# ssd1963.net
KiCad netlist of a schematic drawn in Altium Designer
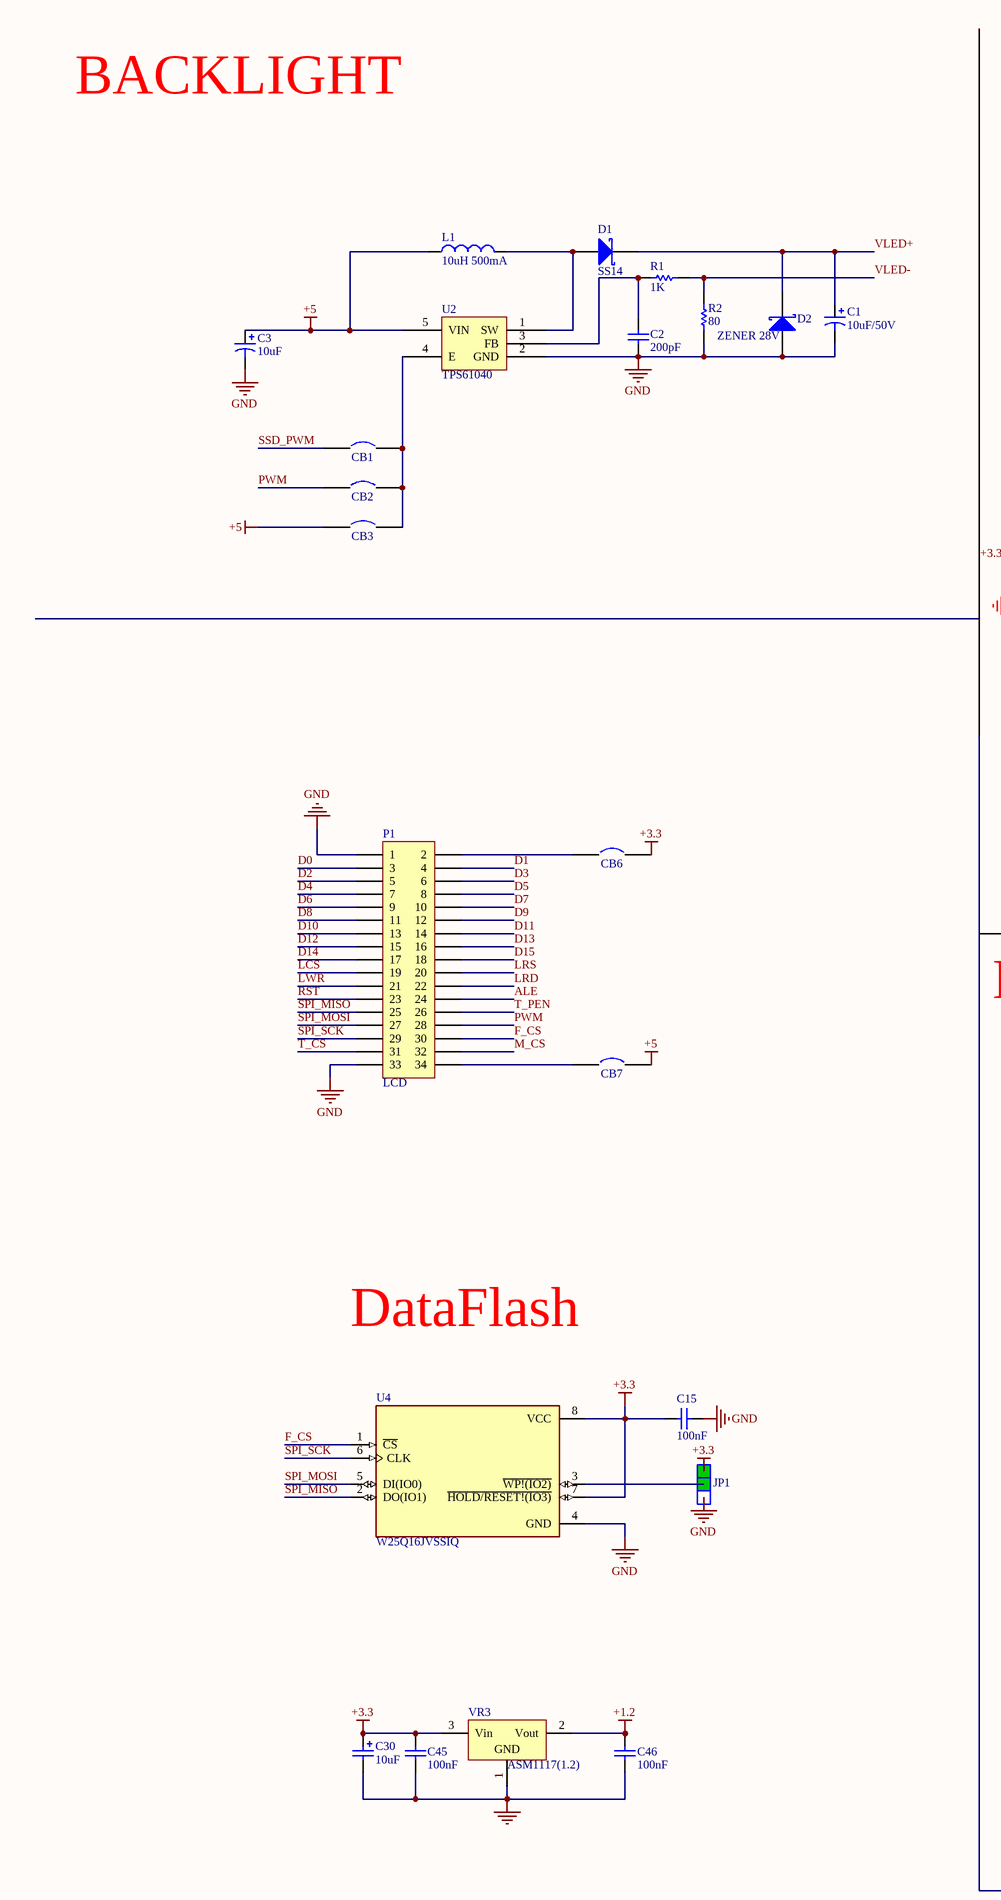
[diagram p0: ssd1963.SchDoc, left]
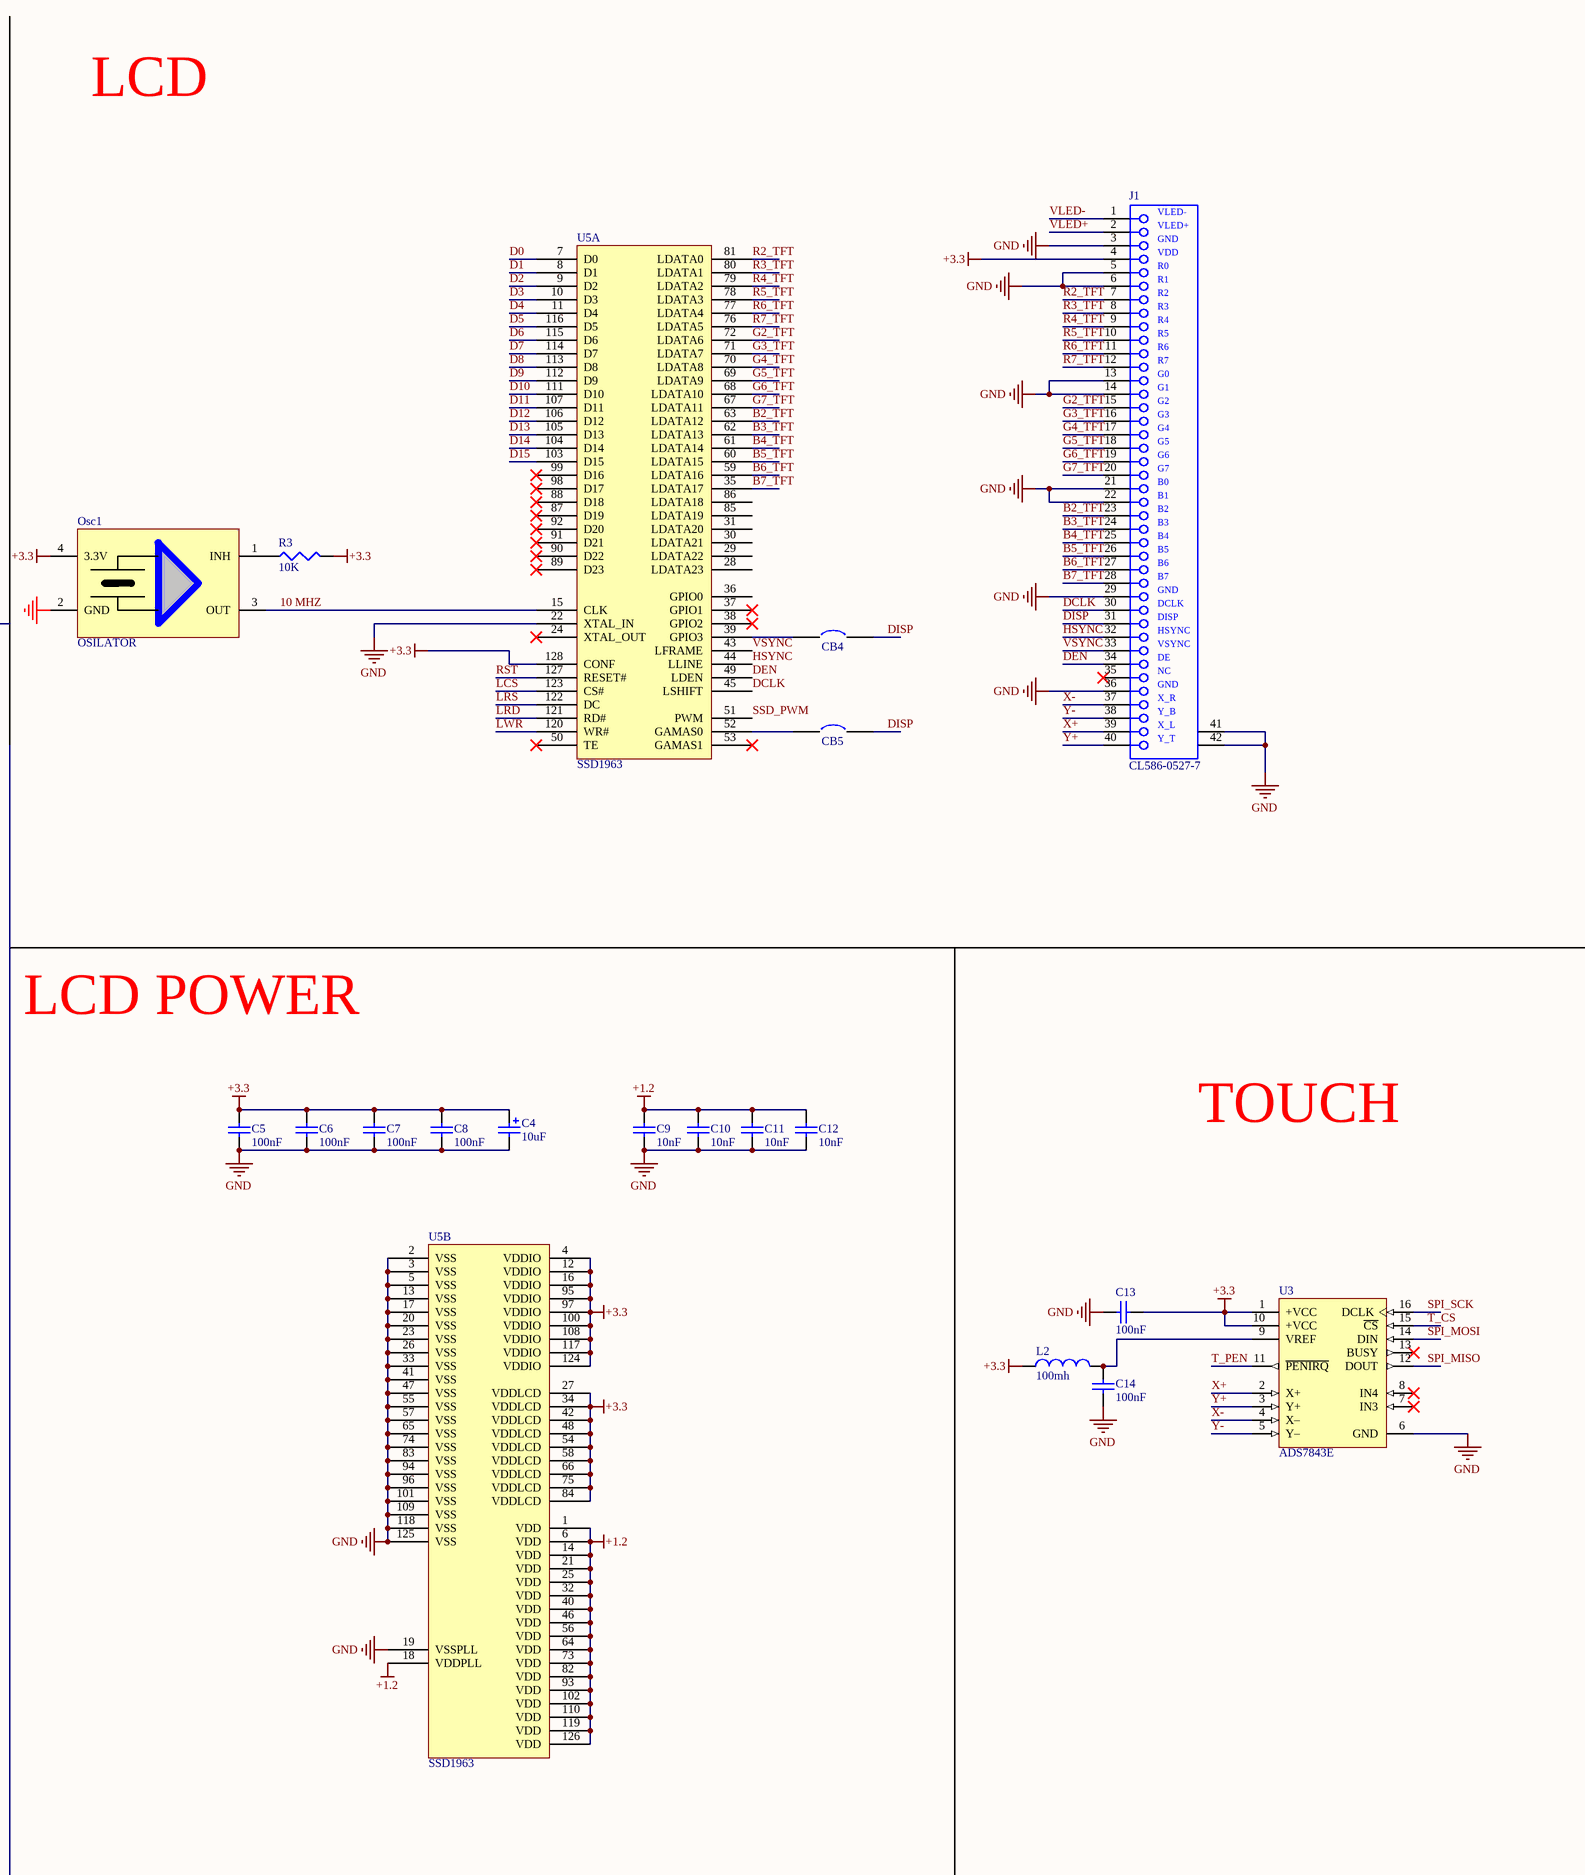
[diagram p1: ssd1963.SchDoc, right]

(export (version "E")
  (design (tool "Eeschema 10.0.6"))
  (components
    (comp (ref "C1")
      (value "10uF/50V")
      (footprint "Tantalium Size A")
      (description "Polarized Capacitor (Radial)")
      (fields (field (name "PUBLISHER") "Altium Limited"))
      (libsource (lib "Miscellaneous Devices") (part "Cap Pol1"))
    )
    (comp (ref "C2")
      (value "200pF")
      (footprint "0805")
      (description "Capacitor (Semiconductor SIM Model)")
      (fields (field (name "PUBLISHER") "Altium Limited"))
      (libsource (lib "Miscellaneous Devices") (part "Cap Semi"))
    )
    (comp (ref "C3")
      (value "10uF")
      (footprint "Tantalium Size A")
      (description "Polarized Capacitor (Radial)")
      (fields (field (name "PUBLISHER") "Altium Limited"))
      (libsource (lib "Miscellaneous Devices") (part "Cap Pol1"))
    )
    (comp (ref "C4")
      (value "10uF")
      (footprint "Tantalium Size A")
      (description "Polarized Capacitor (Radial)")
      (fields (field (name "PUBLISHER") "Altium Limited"))
      (libsource (lib "") (part "Cap Pol1_1"))
    )
    (comp (ref "C5")
      (value "100nF")
      (footprint "0805")
      (description "Capacitor")
      (fields (field (name "PUBLISHER") "Altium Limited"))
      (libsource (lib "Miscellaneous Devices") (part "Cap"))
    )
    (comp (ref "C6")
      (value "100nF")
      (footprint "0805")
      (description "Capacitor")
      (fields (field (name "PUBLISHER") "Altium Limited"))
      (libsource (lib "Miscellaneous Devices") (part "Cap"))
    )
    (comp (ref "C7")
      (value "100nF")
      (footprint "0805")
      (description "Capacitor")
      (fields (field (name "PUBLISHER") "Altium Limited"))
      (libsource (lib "Miscellaneous Devices") (part "Cap"))
    )
    (comp (ref "C8")
      (value "100nF")
      (footprint "0805")
      (description "Capacitor")
      (fields (field (name "PUBLISHER") "Altium Limited"))
      (libsource (lib "Miscellaneous Devices") (part "Cap"))
    )
    (comp (ref "C9")
      (value "10nF")
      (footprint "0805")
      (description "Capacitor")
      (fields (field (name "PUBLISHER") "Altium Limited"))
      (libsource (lib "Miscellaneous Devices") (part "Cap"))
    )
    (comp (ref "C10")
      (value "10nF")
      (footprint "0805")
      (description "Capacitor")
      (fields (field (name "PUBLISHER") "Altium Limited"))
      (libsource (lib "Miscellaneous Devices") (part "Cap"))
    )
    (comp (ref "C11")
      (value "10nF")
      (footprint "0805")
      (description "Capacitor")
      (fields (field (name "PUBLISHER") "Altium Limited"))
      (libsource (lib "Miscellaneous Devices") (part "Cap"))
    )
    (comp (ref "C12")
      (value "10nF")
      (footprint "0805")
      (description "Capacitor")
      (fields (field (name "PUBLISHER") "Altium Limited"))
      (libsource (lib "Miscellaneous Devices") (part "Cap"))
    )
    (comp (ref "C13")
      (value "100nF")
      (footprint "0805")
      (description "Capacitor")
      (fields (field (name "PUBLISHER") "Altium Limited"))
      (libsource (lib "Miscellaneous Devices") (part "Cap"))
    )
    (comp (ref "C14")
      (value "100nF")
      (footprint "0805")
      (description "Capacitor")
      (fields (field (name "PUBLISHER") "Altium Limited"))
      (libsource (lib "Miscellaneous Devices") (part "Cap"))
    )
    (comp (ref "C15")
      (value "100nF")
      (footprint "0805")
      (description "Capacitor")
      (fields (field (name "PUBLISHER") "Altium Limited"))
      (libsource (lib "Miscellaneous Devices") (part "Cap"))
    )
    (comp (ref "C30")
      (value "10uF")
      (footprint "Tantalium Size A")
      (description "Polarized Capacitor (Radial)")
      (fields (field (name "PUBLISHER") "Altium Limited"))
      (libsource (lib "") (part "Cap Pol1_1"))
    )
    (comp (ref "C45")
      (value "100nF")
      (footprint "0805")
      (description "Capacitor")
      (fields (field (name "PUBLISHER") "Altium Limited"))
      (libsource (lib "Miscellaneous Devices") (part "Cap"))
    )
    (comp (ref "C46")
      (value "100nF")
      (footprint "0805")
      (description "Capacitor")
      (fields (field (name "PUBLISHER") "Altium Limited"))
      (libsource (lib "Miscellaneous Devices") (part "Cap"))
    )
    (comp (ref "CB1")
      (value "JUMPER")
      (footprint "0805")
      (description "Circuit Breaker")
      (fields (field (name "PUBLISHER") "Altium Limited"))
      (libsource (lib "Miscellaneous Devices") (part "Circuit Breaker"))
    )
    (comp (ref "CB2")
      (value "JUMPER")
      (footprint "0805")
      (description "Circuit Breaker")
      (fields (field (name "PUBLISHER") "Altium Limited"))
      (libsource (lib "Miscellaneous Devices") (part "Circuit Breaker"))
    )
    (comp (ref "CB3")
      (value "JUMPER")
      (footprint "0805")
      (description "Circuit Breaker")
      (fields (field (name "PUBLISHER") "Altium Limited"))
      (libsource (lib "Miscellaneous Devices") (part "Circuit Breaker"))
    )
    (comp (ref "CB4")
      (value "JUMPER")
      (footprint "0805")
      (description "Circuit Breaker")
      (fields (field (name "PUBLISHER") "Altium Limited"))
      (libsource (lib "Miscellaneous Devices") (part "Circuit Breaker"))
    )
    (comp (ref "CB5")
      (value "JUMPER")
      (footprint "0805")
      (description "Circuit Breaker")
      (fields (field (name "PUBLISHER") "Altium Limited"))
      (libsource (lib "Miscellaneous Devices") (part "Circuit Breaker"))
    )
    (comp (ref "CB6")
      (value "JUMPER")
      (footprint "0805")
      (description "Circuit Breaker")
      (fields (field (name "PUBLISHER") "Altium Limited"))
      (libsource (lib "Miscellaneous Devices") (part "Circuit Breaker"))
    )
    (comp (ref "CB7")
      (value "JUMPER")
      (footprint "0805")
      (description "Circuit Breaker")
      (fields (field (name "PUBLISHER") "Altium Limited"))
      (libsource (lib "Miscellaneous Devices") (part "Circuit Breaker"))
    )
    (comp (ref "D1")
      (value "SS14")
      (footprint "1N4004SMD")
      (description "Schottky Diode")
      (fields (field (name "PUBLISHER") "Altium Limited"))
      (libsource (lib "Miscellaneous Devices") (part "D Schottky"))
    )
    (comp (ref "D2")
      (value "ZENER 28V")
      (footprint "1N4004SMD")
      (description "Schottky Diode")
      (fields (field (name "PUBLISHER") "Altium Limited"))
      (libsource (lib "Miscellaneous Devices") (part "D Schottky"))
    )
    (comp (ref "J1")
      (value "CL586-0527-7")
      (footprint "FPC_40PIN")
      (description "FH12 Series, \"Flip-Lock\" SMT/ZIF FFC/FPC Connector - 0.5mm Spaced Bottom Contact")
      (fields (field (name "PUBLISHER") "Altium Limited"))
      (libsource (lib "Schlib1") (part "CL586-0527-7"))
    )
    (comp (ref "JP1")
      (value "Jumper")
      (footprint "JT3")
      (description "Jumper Selector")
      (libsource (lib "Electrovolt Lib") (part "Jumper Selector"))
    )
    (comp (ref "L1")
      (value "10uH 500mA")
      (footprint "INDUCT100UH B")
      (description "Inductor")
      (fields (field (name "PUBLISHER") "Altium Limited"))
      (libsource (lib "Miscellaneous Devices") (part "Inductor"))
    )
    (comp (ref "L2")
      (value "100mh")
      (footprint "1206")
      (description "Inductor")
      (fields (field (name "PUBLISHER") "Altium Limited"))
      (libsource (lib "Miscellaneous Devices") (part "Inductor"))
    )
    (comp (ref "Osc1")
      (value "OSILATOR")
      (footprint "XTAL_5X7")
      (libsource (lib "New Lib") (part "OSILATOR"))
    )
    (comp (ref "P1")
      (value "LCD")
      (footprint "HDR2X17")
      (description "Header, 17-Pin, Dual row")
      (fields (field (name "PUBLISHER") "Altium Limited"))
      (libsource (lib "Miscellaneous Connectors") (part "Header 17X2"))
    )
    (comp (ref "R1")
      (value "1K")
      (footprint "0805")
      (description "Resistor")
      (fields (field (name "PUBLISHER") "Altium Limited"))
      (libsource (lib "Miscellaneous Devices") (part "Res1"))
    )
    (comp (ref "R2")
      (value "80")
      (footprint "0805")
      (description "Resistor")
      (fields (field (name "PUBLISHER") "Altium Limited"))
      (libsource (lib "Miscellaneous Devices") (part "Res1"))
    )
    (comp (ref "R3")
      (value "10K")
      (footprint "0805")
      (description "Resistor")
      (fields (field (name "PUBLISHER") "Altium Limited"))
      (libsource (lib "Miscellaneous Devices") (part "Res3"))
    )
    (comp (ref "U2")
      (value "TPS61040")
      (footprint "TPS61040")
      (description "Backlight Regulagtor")
      (libsource (lib "Schlib1") (part "TPS61040"))
    )
    (comp (ref "U3")
      (value "ADS7843E")
      (footprint "DBQ016")
      (description "4-Wire Touch Screen Controller, 16-Pin SSOP, Pb-Free")
      (fields (field (name "PUBLISHER") "Altium Limited"))
      (libsource (lib "TI Interface Touch Screen Controller") (part "ADS7843E"))
    )
    (comp (ref "U4")
      (value "W25Q16JVSSIQ")
      (footprint "SOIC127P790X216-8N")
      (description "FLASH - NOR Memory IC 16Mb _2M x 8_ SPI - Quad I/O 133MHz 8-SOIC")
      (fields (field (name "MF") "Winbond Electronics"))
      (libsource (lib "W25Q16JVSSIQ") (part "W25Q16JVSSIQ"))
    )
    (comp (ref "U5")
      (value "SSD1963")
      (footprint "TSQFP40P1600X1600-128N")
      (libsource (lib "Schlib1") (part "SSD1963"))
    )
    (comp (ref "VR3")
      (value "ASM1117(1.2)")
      (footprint "ASM1117")
      (description "Voltage Regulator")
      (fields (field (name "PUBLISHER") "Altium Limited"))
      (libsource (lib "Miscellaneous Devices") (part "Volt Reg_1"))
    )
  )
  (nets
    (net (code "1") (name "+1.2") (class "Default")
      (node (ref "C10") (pin "1") (pinfunction "1_1") (pintype "passive"))
      (node (ref "C11") (pin "1") (pinfunction "1_1") (pintype "passive"))
      (node (ref "C12") (pin "1") (pinfunction "1_1") (pintype "passive"))
      (node (ref "C46") (pin "1") (pinfunction "1_1") (pintype "passive"))
      (node (ref "C9") (pin "1") (pinfunction "1_1") (pintype "passive"))
      (node (ref "U5") (pin "1") (pinfunction "VDD_1") (pintype "power_in"))
      (node (ref "U5") (pin "102") (pinfunction "VDD_102") (pintype "power_in"))
      (node (ref "U5") (pin "110") (pinfunction "VDD_110") (pintype "power_in"))
      (node (ref "U5") (pin "119") (pinfunction "VDD_119") (pintype "power_in"))
      (node (ref "U5") (pin "126") (pinfunction "VDD_126") (pintype "power_in"))
      (node (ref "U5") (pin "14") (pinfunction "VDD_14") (pintype "power_in"))
      (node (ref "U5") (pin "18") (pinfunction "VDDPLL_18") (pintype "power_in"))
      (node (ref "U5") (pin "21") (pinfunction "VDD_21") (pintype "power_in"))
      (node (ref "U5") (pin "25") (pinfunction "VDD_25") (pintype "power_in"))
      (node (ref "U5") (pin "32") (pinfunction "VDD_32") (pintype "power_in"))
      (node (ref "U5") (pin "40") (pinfunction "VDD_40") (pintype "power_in"))
      (node (ref "U5") (pin "46") (pinfunction "VDD_46") (pintype "power_in"))
      (node (ref "U5") (pin "56") (pinfunction "VDD_56") (pintype "power_in"))
      (node (ref "U5") (pin "6") (pinfunction "VDD_6") (pintype "power_in"))
      (node (ref "U5") (pin "64") (pinfunction "VDD_64") (pintype "power_in"))
      (node (ref "U5") (pin "73") (pinfunction "VDD_73") (pintype "power_in"))
      (node (ref "U5") (pin "82") (pinfunction "VDD_82") (pintype "power_in"))
      (node (ref "U5") (pin "93") (pinfunction "VDD_93") (pintype "power_in"))
      (node (ref "VR3") (pin "2") (pinfunction "Vout_2") (pintype "passive"))
    )
    (net (code "2") (name "+3.3") (class "Default")
      (node (ref "C13") (pin "2") (pinfunction "2_2") (pintype "passive"))
      (node (ref "C15") (pin "1") (pinfunction "1_1") (pintype "passive"))
      (node (ref "C30") (pin "1") (pinfunction "1_1") (pintype "passive"))
      (node (ref "C4") (pin "1") (pinfunction "1_1") (pintype "passive"))
      (node (ref "C45") (pin "1") (pinfunction "1_1") (pintype "passive"))
      (node (ref "C5") (pin "1") (pinfunction "1_1") (pintype "passive"))
      (node (ref "C6") (pin "1") (pinfunction "1_1") (pintype "passive"))
      (node (ref "C7") (pin "1") (pinfunction "1_1") (pintype "passive"))
      (node (ref "C8") (pin "1") (pinfunction "1_1") (pintype "passive"))
      (node (ref "CB6") (pin "2") (pinfunction "2_2") (pintype "passive"))
      (node (ref "J1") (pin "4") (pinfunction "4_4") (pintype "passive"))
      (node (ref "JP1") (pin "1") (pinfunction "1_1") (pintype "passive"))
      (node (ref "L2") (pin "1") (pinfunction "1_1") (pintype "passive"))
      (node (ref "Osc1") (pin "4") (pinfunction "3.3V_4") (pintype "passive"))
      (node (ref "R3") (pin "2") (pinfunction "2_2") (pintype "passive"))
      (node (ref "U3") (pin "1") (pinfunction "+VCC_1") (pintype "power_in"))
      (node (ref "U3") (pin "10") (pinfunction "+VCC_10") (pintype "power_in"))
      (node (ref "U4") (pin "7") (pinfunction "~{HOLD/RESET!(IO3)}_7") (pintype "bidirectional"))
      (node (ref "U4") (pin "8") (pinfunction "VCC_8") (pintype "power_in"))
      (node (ref "U5") (pin "100") (pinfunction "VDDIO_100") (pintype "power_in"))
      (node (ref "U5") (pin "108") (pinfunction "VDDIO_108") (pintype "power_in"))
      (node (ref "U5") (pin "117") (pinfunction "VDDIO_117") (pintype "power_in"))
      (node (ref "U5") (pin "12") (pinfunction "VDDIO_12") (pintype "power_in"))
      (node (ref "U5") (pin "124") (pinfunction "VDDIO_124") (pintype "power_in"))
      (node (ref "U5") (pin "128") (pinfunction "CONF_128") (pintype "passive"))
      (node (ref "U5") (pin "16") (pinfunction "VDDIO_16") (pintype "power_in"))
      (node (ref "U5") (pin "27") (pinfunction "VDDLCD_27") (pintype "power_in"))
      (node (ref "U5") (pin "34") (pinfunction "VDDLCD_34") (pintype "power_in"))
      (node (ref "U5") (pin "4") (pinfunction "VDDIO_4") (pintype "power_in"))
      (node (ref "U5") (pin "42") (pinfunction "VDDLCD_42") (pintype "power_in"))
      (node (ref "U5") (pin "48") (pinfunction "VDDLCD_48") (pintype "power_in"))
      (node (ref "U5") (pin "54") (pinfunction "VDDLCD_54") (pintype "power_in"))
      (node (ref "U5") (pin "58") (pinfunction "VDDLCD_58") (pintype "power_in"))
      (node (ref "U5") (pin "66") (pinfunction "VDDLCD_66") (pintype "power_in"))
      (node (ref "U5") (pin "75") (pinfunction "VDDLCD_75") (pintype "power_in"))
      (node (ref "U5") (pin "84") (pinfunction "VDDLCD_84") (pintype "power_in"))
      (node (ref "U5") (pin "95") (pinfunction "VDDIO_95") (pintype "power_in"))
      (node (ref "U5") (pin "97") (pinfunction "VDDIO_97") (pintype "power_in"))
      (node (ref "VR3") (pin "3") (pinfunction "Vin_3") (pintype "passive"))
    )
    (net (code "3") (name "+5") (class "Default")
      (node (ref "C3") (pin "1") (pinfunction "1_1") (pintype "passive"))
      (node (ref "CB3") (pin "1") (pinfunction "1_1") (pintype "passive"))
      (node (ref "CB7") (pin "2") (pinfunction "2_2") (pintype "passive"))
      (node (ref "L1") (pin "1") (pinfunction "1_1") (pintype "passive"))
      (node (ref "U2") (pin "5") (pinfunction "VIN_5") (pintype "passive"))
    )
    (net (code "4") (name "/10 MHZ") (class "Default")
      (node (ref "Osc1") (pin "3") (pinfunction "OUT_3") (pintype "passive"))
      (node (ref "U5") (pin "15") (pinfunction "CLK_15") (pintype "power_in"))
    )
    (net (code "5") (name "/ALE") (class "Default")
      (node (ref "P1") (pin "24") (pinfunction "24_24") (pintype "passive"))
    )
    (net (code "6") (name "/B2_TFT") (class "Default")
      (node (ref "J1") (pin "23") (pinfunction "23_23") (pintype "passive"))
      (node (ref "U5") (pin "63") (pinfunction "LDATA12_63") (pintype "power_in"))
    )
    (net (code "7") (name "/B3_TFT") (class "Default")
      (node (ref "J1") (pin "24") (pinfunction "24_24") (pintype "passive"))
      (node (ref "U5") (pin "62") (pinfunction "LDATA13_62") (pintype "power_in"))
    )
    (net (code "8") (name "/B4_TFT") (class "Default")
      (node (ref "J1") (pin "25") (pinfunction "25_25") (pintype "passive"))
      (node (ref "U5") (pin "61") (pinfunction "LDATA14_61") (pintype "power_in"))
    )
    (net (code "9") (name "/B5_TFT") (class "Default")
      (node (ref "J1") (pin "26") (pinfunction "26_26") (pintype "passive"))
      (node (ref "U5") (pin "60") (pinfunction "LDATA15_60") (pintype "power_in"))
    )
    (net (code "10") (name "/B6_TFT") (class "Default")
      (node (ref "J1") (pin "27") (pinfunction "27_27") (pintype "passive"))
      (node (ref "U5") (pin "59") (pinfunction "LDATA16_59") (pintype "power_in"))
    )
    (net (code "11") (name "/B7_TFT") (class "Default")
      (node (ref "J1") (pin "28") (pinfunction "28_28") (pintype "passive"))
      (node (ref "U5") (pin "35") (pinfunction "LDATA17_35") (pintype "power_in"))
    )
    (net (code "12") (name "/D0") (class "Default")
      (node (ref "P1") (pin "3") (pinfunction "3_3") (pintype "passive"))
      (node (ref "U5") (pin "7") (pinfunction "D0_7") (pintype "power_in"))
    )
    (net (code "13") (name "/D1") (class "Default")
      (node (ref "P1") (pin "4") (pinfunction "4_4") (pintype "passive"))
      (node (ref "U5") (pin "8") (pinfunction "D1_8") (pintype "power_in"))
    )
    (net (code "14") (name "/D2") (class "Default")
      (node (ref "P1") (pin "5") (pinfunction "5_5") (pintype "passive"))
      (node (ref "U5") (pin "9") (pinfunction "D2_9") (pintype "power_in"))
    )
    (net (code "15") (name "/D3") (class "Default")
      (node (ref "P1") (pin "6") (pinfunction "6_6") (pintype "passive"))
      (node (ref "U5") (pin "10") (pinfunction "D3_10") (pintype "power_in"))
    )
    (net (code "16") (name "/D4") (class "Default")
      (node (ref "P1") (pin "7") (pinfunction "7_7") (pintype "passive"))
      (node (ref "U5") (pin "11") (pinfunction "D4_11") (pintype "power_in"))
    )
    (net (code "17") (name "/D5") (class "Default")
      (node (ref "P1") (pin "8") (pinfunction "8_8") (pintype "passive"))
      (node (ref "U5") (pin "116") (pinfunction "D5_116") (pintype "power_in"))
    )
    (net (code "18") (name "/D6") (class "Default")
      (node (ref "P1") (pin "9") (pinfunction "9_9") (pintype "passive"))
      (node (ref "U5") (pin "115") (pinfunction "D6_115") (pintype "power_in"))
    )
    (net (code "19") (name "/D7") (class "Default")
      (node (ref "P1") (pin "10") (pinfunction "10_10") (pintype "passive"))
      (node (ref "U5") (pin "114") (pinfunction "D7_114") (pintype "power_in"))
    )
    (net (code "20") (name "/D8") (class "Default")
      (node (ref "P1") (pin "11") (pinfunction "11_11") (pintype "passive"))
      (node (ref "U5") (pin "113") (pinfunction "D8_113") (pintype "power_in"))
    )
    (net (code "21") (name "/D9") (class "Default")
      (node (ref "P1") (pin "12") (pinfunction "12_12") (pintype "passive"))
      (node (ref "U5") (pin "112") (pinfunction "D9_112") (pintype "power_in"))
    )
    (net (code "22") (name "/D10") (class "Default")
      (node (ref "P1") (pin "13") (pinfunction "13_13") (pintype "passive"))
      (node (ref "U5") (pin "111") (pinfunction "D10_111") (pintype "power_in"))
    )
    (net (code "23") (name "/D11") (class "Default")
      (node (ref "P1") (pin "14") (pinfunction "14_14") (pintype "passive"))
      (node (ref "U5") (pin "107") (pinfunction "D11_107") (pintype "power_in"))
    )
    (net (code "24") (name "/D12") (class "Default")
      (node (ref "P1") (pin "15") (pinfunction "15_15") (pintype "passive"))
      (node (ref "U5") (pin "106") (pinfunction "D12_106") (pintype "power_in"))
    )
    (net (code "25") (name "/D13") (class "Default")
      (node (ref "P1") (pin "16") (pinfunction "16_16") (pintype "passive"))
      (node (ref "U5") (pin "105") (pinfunction "D13_105") (pintype "power_in"))
    )
    (net (code "26") (name "/D14") (class "Default")
      (node (ref "P1") (pin "17") (pinfunction "17_17") (pintype "passive"))
      (node (ref "U5") (pin "104") (pinfunction "D14_104") (pintype "power_in"))
    )
    (net (code "27") (name "/D15") (class "Default")
      (node (ref "P1") (pin "18") (pinfunction "18_18") (pintype "passive"))
      (node (ref "U5") (pin "103") (pinfunction "D15_103") (pintype "power_in"))
    )
    (net (code "28") (name "/DCLK") (class "Default")
      (node (ref "J1") (pin "30") (pinfunction "30_30") (pintype "passive"))
      (node (ref "U5") (pin "45") (pinfunction "LSHIFT_45") (pintype "power_in"))
    )
    (net (code "29") (name "/DEN") (class "Default")
      (node (ref "J1") (pin "34") (pinfunction "34_34") (pintype "passive"))
      (node (ref "U5") (pin "49") (pinfunction "LDEN_49") (pintype "power_in"))
    )
    (net (code "30") (name "/DISP") (class "Default")
      (node (ref "CB4") (pin "2") (pinfunction "2_2") (pintype "passive"))
      (node (ref "CB5") (pin "2") (pinfunction "2_2") (pintype "passive"))
      (node (ref "J1") (pin "31") (pinfunction "31_31") (pintype "passive"))
    )
    (net (code "31") (name "/F_CS") (class "Default")
      (node (ref "P1") (pin "30") (pinfunction "30_30") (pintype "passive"))
      (node (ref "U4") (pin "1") (pinfunction "~{CS}_1") (pintype "input"))
    )
    (net (code "32") (name "/G2_TFT") (class "Default")
      (node (ref "J1") (pin "15") (pinfunction "15_15") (pintype "passive"))
      (node (ref "U5") (pin "72") (pinfunction "LDATA6_72") (pintype "power_in"))
    )
    (net (code "33") (name "/G3_TFT") (class "Default")
      (node (ref "J1") (pin "16") (pinfunction "16_16") (pintype "passive"))
      (node (ref "U5") (pin "71") (pinfunction "LDATA7_71") (pintype "power_in"))
    )
    (net (code "34") (name "/G4_TFT") (class "Default")
      (node (ref "J1") (pin "17") (pinfunction "17_17") (pintype "passive"))
      (node (ref "U5") (pin "70") (pinfunction "LDATA8_70") (pintype "power_in"))
    )
    (net (code "35") (name "/G5_TFT") (class "Default")
      (node (ref "J1") (pin "18") (pinfunction "18_18") (pintype "passive"))
      (node (ref "U5") (pin "69") (pinfunction "LDATA9_69") (pintype "power_in"))
    )
    (net (code "36") (name "/G6_TFT") (class "Default")
      (node (ref "J1") (pin "19") (pinfunction "19_19") (pintype "passive"))
      (node (ref "U5") (pin "68") (pinfunction "LDATA10_68") (pintype "power_in"))
    )
    (net (code "37") (name "/G7_TFT") (class "Default")
      (node (ref "J1") (pin "20") (pinfunction "20_20") (pintype "passive"))
      (node (ref "U5") (pin "67") (pinfunction "LDATA11_67") (pintype "power_in"))
    )
    (net (code "38") (name "/HSYNC") (class "Default")
      (node (ref "J1") (pin "32") (pinfunction "32_32") (pintype "passive"))
      (node (ref "U5") (pin "44") (pinfunction "LLINE_44") (pintype "power_in"))
    )
    (net (code "39") (name "/LCS") (class "Default")
      (node (ref "P1") (pin "19") (pinfunction "19_19") (pintype "passive"))
      (node (ref "U5") (pin "123") (pinfunction "CS#_123") (pintype "passive"))
    )
    (net (code "40") (name "/LRD") (class "Default")
      (node (ref "P1") (pin "22") (pinfunction "22_22") (pintype "passive"))
      (node (ref "U5") (pin "121") (pinfunction "RD#_121") (pintype "passive"))
    )
    (net (code "41") (name "/LRS") (class "Default")
      (node (ref "P1") (pin "20") (pinfunction "20_20") (pintype "passive"))
      (node (ref "U5") (pin "122") (pinfunction "DC_122") (pintype "passive"))
    )
    (net (code "42") (name "/LWR") (class "Default")
      (node (ref "P1") (pin "21") (pinfunction "21_21") (pintype "passive"))
      (node (ref "U5") (pin "120") (pinfunction "WR#_120") (pintype "passive"))
    )
    (net (code "43") (name "/M_CS") (class "Default")
      (node (ref "P1") (pin "32") (pinfunction "32_32") (pintype "passive"))
    )
    (net (code "44") (name "/PWM") (class "Default")
      (node (ref "CB2") (pin "1") (pinfunction "1_1") (pintype "passive"))
      (node (ref "P1") (pin "28") (pinfunction "28_28") (pintype "passive"))
    )
    (net (code "45") (name "/R2_TFT") (class "Default")
      (node (ref "J1") (pin "7") (pinfunction "7_7") (pintype "passive"))
      (node (ref "U5") (pin "81") (pinfunction "LDATA0_81") (pintype "power_in"))
    )
    (net (code "46") (name "/R3_TFT") (class "Default")
      (node (ref "J1") (pin "8") (pinfunction "8_8") (pintype "passive"))
      (node (ref "U5") (pin "80") (pinfunction "LDATA1_80") (pintype "power_in"))
    )
    (net (code "47") (name "/R4_TFT") (class "Default")
      (node (ref "J1") (pin "9") (pinfunction "9_9") (pintype "passive"))
      (node (ref "U5") (pin "79") (pinfunction "LDATA2_79") (pintype "power_in"))
    )
    (net (code "48") (name "/R5_TFT") (class "Default")
      (node (ref "J1") (pin "10") (pinfunction "10_10") (pintype "passive"))
      (node (ref "U5") (pin "78") (pinfunction "LDATA3_78") (pintype "power_in"))
    )
    (net (code "49") (name "/R6_TFT") (class "Default")
      (node (ref "J1") (pin "11") (pinfunction "11_11") (pintype "passive"))
      (node (ref "U5") (pin "77") (pinfunction "LDATA4_77") (pintype "power_in"))
    )
    (net (code "50") (name "/R7_TFT") (class "Default")
      (node (ref "J1") (pin "12") (pinfunction "12_12") (pintype "passive"))
      (node (ref "U5") (pin "76") (pinfunction "LDATA5_76") (pintype "power_in"))
    )
    (net (code "51") (name "/RST") (class "Default")
      (node (ref "P1") (pin "23") (pinfunction "23_23") (pintype "passive"))
      (node (ref "U5") (pin "127") (pinfunction "RESET#_127") (pintype "passive"))
    )
    (net (code "52") (name "/SPI_MISO") (class "Default")
      (node (ref "P1") (pin "25") (pinfunction "25_25") (pintype "passive"))
      (node (ref "U3") (pin "12") (pinfunction "DOUT_12") (pintype "output"))
      (node (ref "U4") (pin "2") (pinfunction "DO(IO1)_2") (pintype "bidirectional"))
    )
    (net (code "53") (name "/SPI_MOSI") (class "Default")
      (node (ref "P1") (pin "27") (pinfunction "27_27") (pintype "passive"))
      (node (ref "U3") (pin "14") (pinfunction "DIN_14") (pintype "input"))
      (node (ref "U4") (pin "5") (pinfunction "DI(IO0)_5") (pintype "bidirectional"))
    )
    (net (code "54") (name "/SPI_SCK") (class "Default")
      (node (ref "P1") (pin "29") (pinfunction "29_29") (pintype "passive"))
      (node (ref "U3") (pin "16") (pinfunction "DCLK_16") (pintype "input"))
      (node (ref "U4") (pin "6") (pinfunction "CLK_6") (pintype "input"))
    )
    (net (code "55") (name "/SSD_PWM") (class "Default")
      (node (ref "CB1") (pin "1") (pinfunction "1_1") (pintype "passive"))
      (node (ref "U5") (pin "51") (pinfunction "PWM_51") (pintype "power_in"))
    )
    (net (code "56") (name "/T_CS") (class "Default")
      (node (ref "P1") (pin "31") (pinfunction "31_31") (pintype "passive"))
      (node (ref "U3") (pin "15") (pinfunction "~{CS}_15") (pintype "input"))
    )
    (net (code "57") (name "/T_PEN") (class "Default")
      (node (ref "P1") (pin "26") (pinfunction "26_26") (pintype "passive"))
      (node (ref "U3") (pin "11") (pinfunction "~{PENIRQ}_11") (pintype "output"))
    )
    (net (code "58") (name "/VLED+") (class "Default")
      (node (ref "C1") (pin "1") (pinfunction "1_1") (pintype "passive"))
      (node (ref "D1") (pin "2") (pinfunction "K_2") (pintype "passive"))
      (node (ref "D2") (pin "2") (pinfunction "K_2") (pintype "passive"))
      (node (ref "J1") (pin "2") (pinfunction "2_2") (pintype "passive"))
    )
    (net (code "59") (name "/VLED-") (class "Default")
      (node (ref "J1") (pin "1") (pinfunction "1_1") (pintype "passive"))
      (node (ref "R1") (pin "2") (pinfunction "2_2") (pintype "passive"))
      (node (ref "R2") (pin "2") (pinfunction "2_2") (pintype "passive"))
    )
    (net (code "60") (name "/VSYNC") (class "Default")
      (node (ref "J1") (pin "33") (pinfunction "33_33") (pintype "passive"))
      (node (ref "U5") (pin "43") (pinfunction "LFRAME_43") (pintype "power_in"))
    )
    (net (code "61") (name "/X+") (class "Default")
      (node (ref "J1") (pin "39") (pinfunction "39_39") (pintype "passive"))
      (node (ref "U3") (pin "2") (pinfunction "X+_2") (pintype "input"))
    )
    (net (code "62") (name "/X-") (class "Default")
      (node (ref "J1") (pin "37") (pinfunction "37_37") (pintype "passive"))
      (node (ref "U3") (pin "4") (pinfunction "X–_4") (pintype "input"))
    )
    (net (code "63") (name "/Y+") (class "Default")
      (node (ref "J1") (pin "40") (pinfunction "40_40") (pintype "passive"))
      (node (ref "U3") (pin "3") (pinfunction "Y+_3") (pintype "input"))
    )
    (net (code "64") (name "/Y-") (class "Default")
      (node (ref "J1") (pin "38") (pinfunction "38_38") (pintype "passive"))
      (node (ref "U3") (pin "5") (pinfunction "Y–_5") (pintype "input"))
    )
    (net (code "65") (name "GND") (class "Default")
      (node (ref "C1") (pin "2") (pinfunction "2_2") (pintype "passive"))
      (node (ref "C10") (pin "2") (pinfunction "2_2") (pintype "passive"))
      (node (ref "C11") (pin "2") (pinfunction "2_2") (pintype "passive"))
      (node (ref "C12") (pin "2") (pinfunction "2_2") (pintype "passive"))
      (node (ref "C13") (pin "1") (pinfunction "1_1") (pintype "passive"))
      (node (ref "C14") (pin "1") (pinfunction "1_1") (pintype "passive"))
      (node (ref "C15") (pin "2") (pinfunction "2_2") (pintype "passive"))
      (node (ref "C2") (pin "1") (pinfunction "1_1") (pintype "passive"))
      (node (ref "C3") (pin "2") (pinfunction "2_2") (pintype "passive"))
      (node (ref "C30") (pin "2") (pinfunction "2_2") (pintype "passive"))
      (node (ref "C4") (pin "2") (pinfunction "2_2") (pintype "passive"))
      (node (ref "C45") (pin "2") (pinfunction "2_2") (pintype "passive"))
      (node (ref "C46") (pin "2") (pinfunction "2_2") (pintype "passive"))
      (node (ref "C5") (pin "2") (pinfunction "2_2") (pintype "passive"))
      (node (ref "C6") (pin "2") (pinfunction "2_2") (pintype "passive"))
      (node (ref "C7") (pin "2") (pinfunction "2_2") (pintype "passive"))
      (node (ref "C8") (pin "2") (pinfunction "2_2") (pintype "passive"))
      (node (ref "C9") (pin "2") (pinfunction "2_2") (pintype "passive"))
      (node (ref "D2") (pin "1") (pinfunction "A_1") (pintype "passive"))
      (node (ref "J1") (pin "13") (pinfunction "13_13") (pintype "passive"))
      (node (ref "J1") (pin "14") (pinfunction "14_14") (pintype "passive"))
      (node (ref "J1") (pin "21") (pinfunction "21_21") (pintype "passive"))
      (node (ref "J1") (pin "22") (pinfunction "22_22") (pintype "passive"))
      (node (ref "J1") (pin "29") (pinfunction "29_29") (pintype "passive"))
      (node (ref "J1") (pin "3") (pinfunction "3_3") (pintype "passive"))
      (node (ref "J1") (pin "36") (pinfunction "36_36") (pintype "passive"))
      (node (ref "J1") (pin "41") (pinfunction "MH1_41") (pintype "passive"))
      (node (ref "J1") (pin "42") (pinfunction "MH2_42") (pintype "passive"))
      (node (ref "J1") (pin "5") (pinfunction "5_5") (pintype "passive"))
      (node (ref "J1") (pin "6") (pinfunction "6_6") (pintype "passive"))
      (node (ref "JP1") (pin "3") (pinfunction "3_3") (pintype "passive"))
      (node (ref "Osc1") (pin "2") (pinfunction "GND_2") (pintype "passive"))
      (node (ref "P1") (pin "1") (pinfunction "1_1") (pintype "passive"))
      (node (ref "P1") (pin "33") (pinfunction "33_33") (pintype "passive"))
      (node (ref "R2") (pin "1") (pinfunction "1_1") (pintype "passive"))
      (node (ref "U2") (pin "2") (pinfunction "GND_2") (pintype "passive"))
      (node (ref "U3") (pin "6") (pinfunction "GND_6") (pintype "power_in"))
      (node (ref "U4") (pin "4") (pinfunction "GND_4") (pintype "power_in"))
      (node (ref "U5") (pin "101") (pinfunction "VSS_101") (pintype "power_in"))
      (node (ref "U5") (pin "109") (pinfunction "VSS_109") (pintype "power_in"))
      (node (ref "U5") (pin "118") (pinfunction "VSS_118") (pintype "power_in"))
      (node (ref "U5") (pin "125") (pinfunction "VSS_125") (pintype "power_in"))
      (node (ref "U5") (pin "13") (pinfunction "VSS_13") (pintype "power_in"))
      (node (ref "U5") (pin "17") (pinfunction "VSS_17") (pintype "power_in"))
      (node (ref "U5") (pin "19") (pinfunction "VSSPLL_19") (pintype "power_in"))
      (node (ref "U5") (pin "2") (pinfunction "VSS_2") (pintype "power_in"))
      (node (ref "U5") (pin "20") (pinfunction "VSS_20") (pintype "power_in"))
      (node (ref "U5") (pin "22") (pinfunction "XTAL_IN_22") (pintype "power_in"))
      (node (ref "U5") (pin "23") (pinfunction "VSS_23") (pintype "power_in"))
      (node (ref "U5") (pin "26") (pinfunction "VSS_26") (pintype "power_in"))
      (node (ref "U5") (pin "3") (pinfunction "VSS_3") (pintype "power_in"))
      (node (ref "U5") (pin "33") (pinfunction "VSS_33") (pintype "power_in"))
      (node (ref "U5") (pin "41") (pinfunction "VSS_41") (pintype "power_in"))
      (node (ref "U5") (pin "47") (pinfunction "VSS_47") (pintype "power_in"))
      (node (ref "U5") (pin "5") (pinfunction "VSS_5") (pintype "power_in"))
      (node (ref "U5") (pin "55") (pinfunction "VSS_55") (pintype "power_in"))
      (node (ref "U5") (pin "57") (pinfunction "VSS_57") (pintype "power_in"))
      (node (ref "U5") (pin "65") (pinfunction "VSS_65") (pintype "power_in"))
      (node (ref "U5") (pin "74") (pinfunction "VSS_74") (pintype "power_in"))
      (node (ref "U5") (pin "83") (pinfunction "VSS_83") (pintype "power_in"))
      (node (ref "U5") (pin "94") (pinfunction "VSS_94") (pintype "power_in"))
      (node (ref "U5") (pin "96") (pinfunction "VSS_96") (pintype "power_in"))
      (node (ref "VR3") (pin "1") (pinfunction "GND_1") (pintype "passive"))
    )
    (net (code "66") (name "Net-(CB6-Pad1)") (class "Default")
      (node (ref "CB6") (pin "1") (pinfunction "1_1") (pintype "passive"))
      (node (ref "P1") (pin "2") (pinfunction "2_2") (pintype "passive"))
    )
    (net (code "67") (name "Net-(CB7-Pad1)") (class "Default")
      (node (ref "CB7") (pin "1") (pinfunction "1_1") (pintype "passive"))
      (node (ref "P1") (pin "34") (pinfunction "34_34") (pintype "passive"))
    )
    (net (code "68") (name "Net-(D1-A)") (class "Default")
      (node (ref "D1") (pin "1") (pinfunction "A_1") (pintype "passive"))
      (node (ref "L1") (pin "2") (pinfunction "2_2") (pintype "passive"))
      (node (ref "U2") (pin "1") (pinfunction "SW_1") (pintype "passive"))
    )
    (net (code "69") (name "Net-(Osc1-INH)") (class "Default")
      (node (ref "Osc1") (pin "1") (pinfunction "INH_1") (pintype "passive"))
      (node (ref "R3") (pin "1") (pinfunction "1_1") (pintype "passive"))
    )
    (net (code "70") (name "Net-(U2-E)") (class "Default")
      (node (ref "CB1") (pin "2") (pinfunction "2_2") (pintype "passive"))
      (node (ref "CB2") (pin "2") (pinfunction "2_2") (pintype "passive"))
      (node (ref "CB3") (pin "2") (pinfunction "2_2") (pintype "passive"))
      (node (ref "U2") (pin "4") (pinfunction "E_4") (pintype "passive"))
    )
    (net (code "71") (name "Net-(U2-FB)") (class "Default")
      (node (ref "C2") (pin "2") (pinfunction "2_2") (pintype "passive"))
      (node (ref "R1") (pin "1") (pinfunction "1_1") (pintype "passive"))
      (node (ref "U2") (pin "3") (pinfunction "FB_3") (pintype "passive"))
    )
    (net (code "72") (name "Net-(U3-VREF)") (class "Default")
      (node (ref "C14") (pin "2") (pinfunction "2_2") (pintype "passive"))
      (node (ref "L2") (pin "2") (pinfunction "2_2") (pintype "passive"))
      (node (ref "U3") (pin "9") (pinfunction "VREF_9") (pintype "power_in"))
    )
    (net (code "73") (name "Net-(U4-~{WP!(IO2)})") (class "Default")
      (node (ref "JP1") (pin "2") (pinfunction "2_2") (pintype "passive"))
      (node (ref "U4") (pin "3") (pinfunction "~{WP!(IO2)}_3") (pintype "bidirectional"))
    )
    (net (code "74") (name "Net-(U5A-GAMAS0)") (class "Default")
      (node (ref "CB5") (pin "1") (pinfunction "1_1") (pintype "passive"))
      (node (ref "U5") (pin "52") (pinfunction "GAMAS0_52") (pintype "power_in"))
    )
    (net (code "75") (name "Net-(U5A-GPIO3)") (class "Default")
      (node (ref "CB4") (pin "1") (pinfunction "1_1") (pintype "passive"))
      (node (ref "U5") (pin "39") (pinfunction "GPIO3_39") (pintype "power_in"))
    )
    (net (code "76") (name "unconnected-(J1-Pad35)") (class "Default")
      (node (ref "J1") (pin "35") (pinfunction "35_35") (pintype "passive+no_connect"))
    )
    (net (code "77") (name "unconnected-(U3-BUSY-Pad13)") (class "Default")
      (node (ref "U3") (pin "13") (pinfunction "BUSY_13") (pintype "output+no_connect"))
    )
    (net (code "78") (name "unconnected-(U3-IN3-Pad7)") (class "Default")
      (node (ref "U3") (pin "7") (pinfunction "IN3_7") (pintype "input+no_connect"))
    )
    (net (code "79") (name "unconnected-(U3-IN4-Pad8)") (class "Default")
      (node (ref "U3") (pin "8") (pinfunction "IN4_8") (pintype "input+no_connect"))
    )
    (net (code "80") (name "unconnected-(U5A-D16-Pad99)") (class "Default")
      (node (ref "U5") (pin "99") (pinfunction "D16_99") (pintype "power_in+no_connect"))
    )
    (net (code "81") (name "unconnected-(U5A-D17-Pad98)") (class "Default")
      (node (ref "U5") (pin "98") (pinfunction "D17_98") (pintype "power_in+no_connect"))
    )
    (net (code "82") (name "unconnected-(U5A-D18-Pad88)") (class "Default")
      (node (ref "U5") (pin "88") (pinfunction "D18_88") (pintype "power_in+no_connect"))
    )
    (net (code "83") (name "unconnected-(U5A-D19-Pad87)") (class "Default")
      (node (ref "U5") (pin "87") (pinfunction "D19_87") (pintype "power_in+no_connect"))
    )
    (net (code "84") (name "unconnected-(U5A-D20-Pad92)") (class "Default")
      (node (ref "U5") (pin "92") (pinfunction "D20_92") (pintype "power_in+no_connect"))
    )
    (net (code "85") (name "unconnected-(U5A-D21-Pad91)") (class "Default")
      (node (ref "U5") (pin "91") (pinfunction "D21_91") (pintype "power_in+no_connect"))
    )
    (net (code "86") (name "unconnected-(U5A-D22-Pad90)") (class "Default")
      (node (ref "U5") (pin "90") (pinfunction "D22_90") (pintype "power_in+no_connect"))
    )
    (net (code "87") (name "unconnected-(U5A-D23-Pad89)") (class "Default")
      (node (ref "U5") (pin "89") (pinfunction "D23_89") (pintype "power_in+no_connect"))
    )
    (net (code "88") (name "unconnected-(U5A-GAMAS1-Pad53)") (class "Default")
      (node (ref "U5") (pin "53") (pinfunction "GAMAS1_53") (pintype "power_in+no_connect"))
    )
    (net (code "89") (name "unconnected-(U5A-GPIO0-Pad36)") (class "Default")
      (node (ref "U5") (pin "36") (pinfunction "GPIO0_36") (pintype "power_in"))
    )
    (net (code "90") (name "unconnected-(U5A-GPIO1-Pad37)") (class "Default")
      (node (ref "U5") (pin "37") (pinfunction "GPIO1_37") (pintype "power_in+no_connect"))
    )
    (net (code "91") (name "unconnected-(U5A-GPIO2-Pad38)") (class "Default")
      (node (ref "U5") (pin "38") (pinfunction "GPIO2_38") (pintype "power_in+no_connect"))
    )
    (net (code "92") (name "unconnected-(U5A-LDATA18-Pad86)") (class "Default")
      (node (ref "U5") (pin "86") (pinfunction "LDATA18_86") (pintype "power_in"))
    )
    (net (code "93") (name "unconnected-(U5A-LDATA19-Pad85)") (class "Default")
      (node (ref "U5") (pin "85") (pinfunction "LDATA19_85") (pintype "power_in"))
    )
    (net (code "94") (name "unconnected-(U5A-LDATA20-Pad31)") (class "Default")
      (node (ref "U5") (pin "31") (pinfunction "LDATA20_31") (pintype "power_in"))
    )
    (net (code "95") (name "unconnected-(U5A-LDATA21-Pad30)") (class "Default")
      (node (ref "U5") (pin "30") (pinfunction "LDATA21_30") (pintype "power_in"))
    )
    (net (code "96") (name "unconnected-(U5A-LDATA22-Pad29)") (class "Default")
      (node (ref "U5") (pin "29") (pinfunction "LDATA22_29") (pintype "power_in"))
    )
    (net (code "97") (name "unconnected-(U5A-LDATA23-Pad28)") (class "Default")
      (node (ref "U5") (pin "28") (pinfunction "LDATA23_28") (pintype "power_in"))
    )
    (net (code "98") (name "unconnected-(U5A-TE-Pad50)") (class "Default")
      (node (ref "U5") (pin "50") (pinfunction "TE_50") (pintype "passive+no_connect"))
    )
    (net (code "99") (name "unconnected-(U5A-XTAL_OUT-Pad24)") (class "Default")
      (node (ref "U5") (pin "24") (pinfunction "XTAL_OUT_24") (pintype "power_in+no_connect"))
    )
  )
)
